# EDU_High-Speed-Design_Flash.net
KiCad netlist of a schematic drawn in Altium Designer
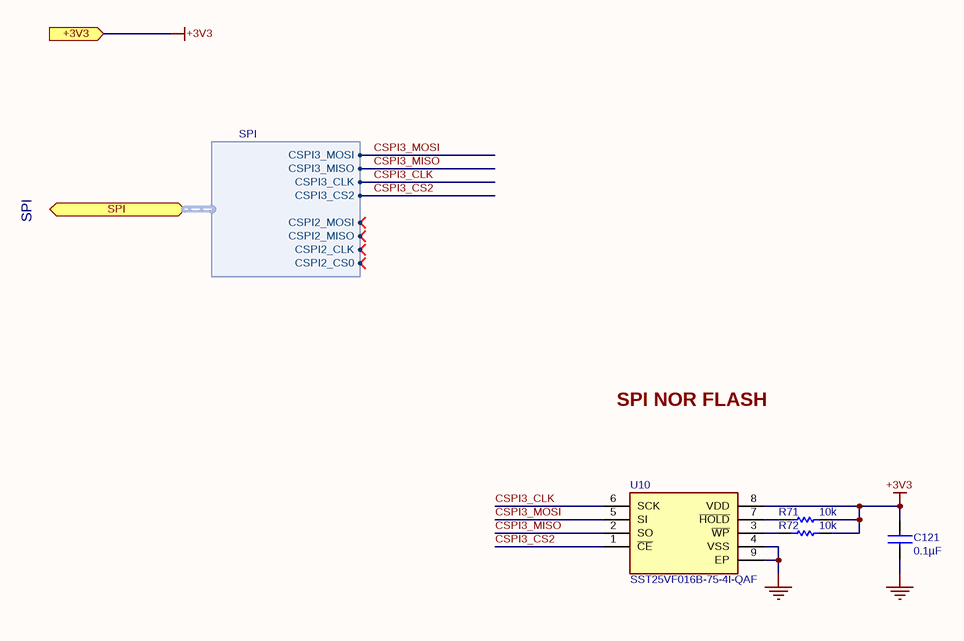
[diagram p0: EDU_High-Speed-Design_Flash.SchDoc]

(export (version "E")
  (design (tool "Eeschema 10.0.6"))
  (components
    (comp (ref "C121")
      (value "0.1µF")
      (footprint "C0402")
      (description "CAP CER .10UF 50V X5R 10% 0402")
      (fields (field (name "VOLTAGE") "50V"))
      (libsource (lib "EDU_High-Speed-Design") (part "C1005X5R1H104K"))
    )
    (comp (ref "R71")
      (value "10k")
      (footprint "R0402")
      (description "RES 10.0K OHM 1/16W 1% 0402 SMD")
      (libsource (lib "EDU_High-Speed-Design") (part "RC0402FR-0710KL"))
    )
    (comp (ref "R72")
      (value "10k")
      (footprint "R0402")
      (description "RES 10.0K OHM 1/16W 1% 0402 SMD")
      (libsource (lib "EDU_High-Speed-Design") (part "RC0402FR-0710KL"))
    )
    (comp (ref "U10")
      (value "SST25VF016B-75-4I-QAF")
      (footprint "SST25VF016B")
      (description "IC FLASH 16MBIT 75MHZ 8WSON")
      (libsource (lib "EDU_High-Speed-Design") (part "SST25VF016B-75-4I-QAF"))
    )
  )
  (nets
    (net (code "2") (name "+3V3") (class "Default")
      (node (ref "C121") (pin "1") (pinfunction "1_1") (pintype "passive"))
      (node (ref "R71") (pin "2") (pinfunction "2_2") (pintype "passive"))
      (node (ref "R72") (pin "2") (pinfunction "2_2") (pintype "passive"))
      (node (ref "U10") (pin "8") (pinfunction "VDD_8") (pintype "passive"))
    )
    (net (code "3") (name "/CSPI3_CLK") (class "Default")
      (node (ref "U10") (pin "6") (pinfunction "SCK_6") (pintype "passive"))
    )
    (net (code "4") (name "/CSPI3_CS2") (class "Default")
      (node (ref "U10") (pin "1") (pinfunction "~{CE}_1") (pintype "passive"))
    )
    (net (code "5") (name "/CSPI3_MISO") (class "Default")
      (node (ref "U10") (pin "2") (pinfunction "SO_2") (pintype "passive"))
    )
    (net (code "6") (name "/CSPI3_MOSI") (class "Default")
      (node (ref "U10") (pin "5") (pinfunction "SI_5") (pintype "passive"))
    )
    (net (code "8") (name "GND") (class "Default")
      (node (ref "C121") (pin "2") (pinfunction "2_2") (pintype "passive"))
      (node (ref "U10") (pin "4") (pinfunction "VSS_4") (pintype "passive"))
      (node (ref "U10") (pin "9") (pinfunction "EP_9") (pintype "passive"))
    )
    (net (code "9") (name "Net-(U10-~{HOLD})") (class "Default")
      (node (ref "R71") (pin "1") (pinfunction "1_1") (pintype "passive"))
      (node (ref "U10") (pin "7") (pinfunction "~{HOLD}_7") (pintype "passive"))
    )
    (net (code "10") (name "Net-(U10-~{WP})") (class "Default")
      (node (ref "R72") (pin "1") (pinfunction "1_1") (pintype "passive"))
      (node (ref "U10") (pin "3") (pinfunction "~{WP}_3") (pintype "passive"))
    )
  )
)
